# martinez.net
KiCad netlist of a schematic drawn in EAGLE
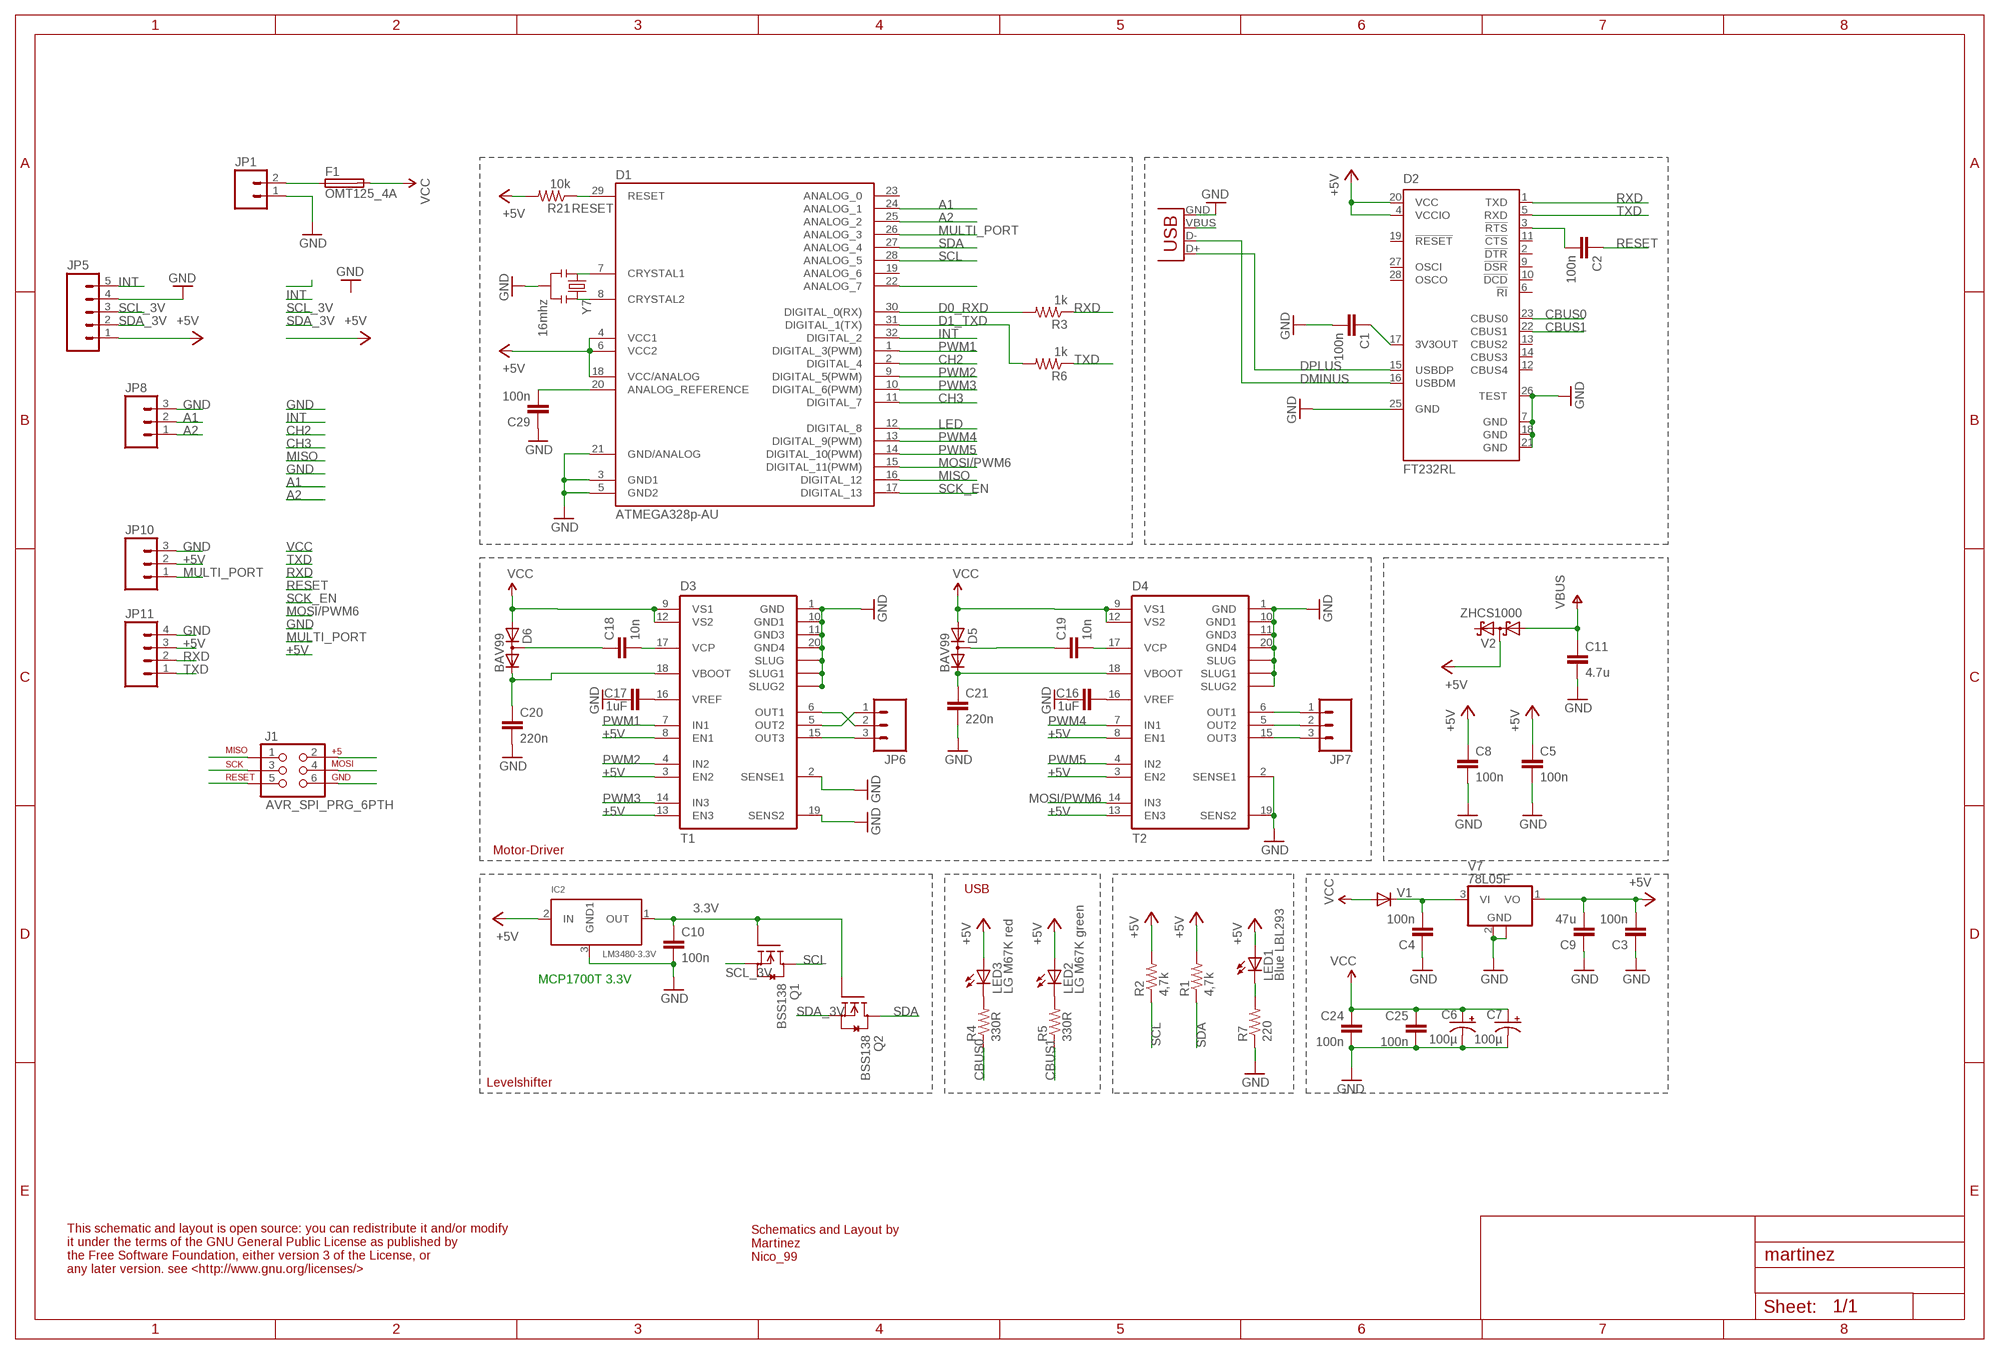
[diagram p0: schematic, sheet 1]

(export (version "E")
  (design (tool "Eeschema 10.0.6"))
  (components
    (comp (ref "C1")
      (value "100n")
      (footprint "eagle-import:0805")
      (libsource (lib "eagle-import") (part "CAP0805"))
    )
    (comp (ref "C2")
      (value "100n")
      (footprint "eagle-import:0805")
      (libsource (lib "eagle-import") (part "CAP0805"))
    )
    (comp (ref "C3")
      (value "100n")
      (footprint "eagle-import:0805")
      (libsource (lib "eagle-import") (part "CAP0805"))
    )
    (comp (ref "C4")
      (value "100n")
      (footprint "eagle-import:0805")
      (libsource (lib "eagle-import") (part "CAP0805"))
    )
    (comp (ref "C5")
      (value "100n")
      (footprint "eagle-import:0805")
      (libsource (lib "eagle-import") (part "CAP0805"))
    )
    (comp (ref "C6")
      (value "100µ")
      (footprint "eagle-import:PANASONIC_D")
      (libsource (lib "eagle-import") (part "CAP_POLD"))
    )
    (comp (ref "C7")
      (value "100µ")
      (footprint "eagle-import:PANASONIC_D")
      (libsource (lib "eagle-import") (part "CAP_POLD"))
    )
    (comp (ref "C8")
      (value "100n")
      (footprint "eagle-import:0805")
      (libsource (lib "eagle-import") (part "CAP0805"))
    )
    (comp (ref "C9")
      (value "47u")
      (footprint "eagle-import:C1210")
      (libsource (lib "eagle-import") (part "C-EUC1210"))
    )
    (comp (ref "C10")
      (value "100n")
      (footprint "eagle-import:0805")
      (libsource (lib "eagle-import") (part "CAP0805"))
    )
    (comp (ref "C11")
      (value "4.7u")
      (footprint "eagle-import:0805")
      (libsource (lib "eagle-import") (part "CAP0805"))
    )
    (comp (ref "C16")
      (value "1uF")
      (footprint "eagle-import:0805")
      (libsource (lib "eagle-import") (part "CAP0805"))
    )
    (comp (ref "C17")
      (value "1uF")
      (footprint "eagle-import:0805")
      (libsource (lib "eagle-import") (part "CAP0805"))
    )
    (comp (ref "C18")
      (value "10n")
      (footprint "eagle-import:0805")
      (libsource (lib "eagle-import") (part "CAP0805"))
    )
    (comp (ref "C19")
      (value "10n")
      (footprint "eagle-import:0805")
      (libsource (lib "eagle-import") (part "CAP0805"))
    )
    (comp (ref "C20")
      (value "220n")
      (footprint "eagle-import:0805")
      (libsource (lib "eagle-import") (part "CAP0805"))
    )
    (comp (ref "C21")
      (value "220n")
      (footprint "eagle-import:0805")
      (libsource (lib "eagle-import") (part "CAP0805"))
    )
    (comp (ref "C24")
      (value "100n")
      (footprint "eagle-import:0805")
      (libsource (lib "eagle-import") (part "CAP0805"))
    )
    (comp (ref "C25")
      (value "100n")
      (footprint "eagle-import:0805")
      (libsource (lib "eagle-import") (part "CAP0805"))
    )
    (comp (ref "C29")
      (value "100n")
      (footprint "eagle-import:0805")
      (libsource (lib "eagle-import") (part "CAP0805"))
    )
    (comp (ref "D1")
      (value "ATMEGA328p-AU")
      (footprint "eagle-import:TQFP32-08")
      (libsource (lib "eagle-import") (part "ATMEGA168-AU"))
    )
    (comp (ref "D2")
      (value "FT232RL")
      (footprint "eagle-import:SSOP28")
      (libsource (lib "eagle-import") (part "FT232RL"))
    )
    (comp (ref "D3")
      (value "T1")
      (footprint "eagle-import:SO20POWER2")
      (libsource (lib "eagle-import") (part "L6234"))
    )
    (comp (ref "D4")
      (value "T2")
      (footprint "eagle-import:SO20POWER2")
      (libsource (lib "eagle-import") (part "L6234"))
    )
    (comp (ref "D5")
      (value "BAV99")
      (footprint "eagle-import:SOT23")
      (libsource (lib "eagle-import") (part "BAV199"))
    )
    (comp (ref "D6")
      (value "BAV99")
      (footprint "eagle-import:SOT23")
      (libsource (lib "eagle-import") (part "BAV199"))
    )
    (comp (ref "F1")
      (value "OMT125_4A")
      (footprint "eagle-import:OMT125_11MM")
      (libsource (lib "eagle-import") (part "OMT125_11MM"))
    )
    (comp (ref "IC2")
      (value "LM3480-3.3V")
      (footprint "eagle-import:SOT23")
      (libsource (lib "eagle-import") (part "VREG_MULTI2"))
    )
    (comp (ref "J1")
      (value "AVR_SPI_PRG_6PTH")
      (footprint "eagle-import:2X3")
      (libsource (lib "eagle-import") (part "AVR_SPI_PRG_6PTH"))
    )
    (comp (ref "JP1")
      (value "M02PTH")
      (footprint "eagle-import:1X02")
      (libsource (lib "eagle-import") (part "M02PTH"))
    )
    (comp (ref "JP5")
      (value "M05PTH")
      (footprint "eagle-import:1X05")
      (libsource (lib "eagle-import") (part "M05PTH"))
    )
    (comp (ref "JP6")
      (value "M03PTH")
      (footprint "eagle-import:1X03")
      (libsource (lib "eagle-import") (part "M03PTH"))
    )
    (comp (ref "JP7")
      (value "M03PTH")
      (footprint "eagle-import:1X03")
      (libsource (lib "eagle-import") (part "M03PTH"))
    )
    (comp (ref "JP8")
      (value "M031X03_NO_SILK")
      (footprint "eagle-import:1X03_NO_SILK")
      (libsource (lib "eagle-import") (part "M031X03_NO_SILK"))
    )
    (comp (ref "JP10")
      (value "M031X03_NO_SILK")
      (footprint "eagle-import:1X03_NO_SILK")
      (libsource (lib "eagle-import") (part "M031X03_NO_SILK"))
    )
    (comp (ref "JP11")
      (value "M041X04_NO_SILK")
      (footprint "eagle-import:1X04_NO_SILK")
      (libsource (lib "eagle-import") (part "M041X04_NO_SILK"))
    )
    (comp (ref "LED1")
      (value "Blue LBL293")
      (footprint "eagle-import:CHIP-LED0603")
      (libsource (lib "eagle-import") (part "LEDCHIP-LED0603"))
    )
    (comp (ref "LED2")
      (value "LG M67K green")
      (footprint "eagle-import:CHIP-LED0805")
      (libsource (lib "eagle-import") (part "LEDCHIP-LED0805"))
    )
    (comp (ref "LED3")
      (value "LG M67K red")
      (footprint "eagle-import:CHIP-LED0805")
      (libsource (lib "eagle-import") (part "LEDCHIP-LED0805"))
    )
    (comp (ref "Q1")
      (value "BSS138")
      (footprint "eagle-import:SOT23")
      (libsource (lib "eagle-import") (part "BSS138"))
    )
    (comp (ref "Q2")
      (value "BSS138")
      (footprint "eagle-import:SOT23")
      (libsource (lib "eagle-import") (part "BSS138"))
    )
    (comp (ref "R1")
      (value "4,7k")
      (footprint "eagle-import:0805")
      (libsource (lib "eagle-import") (part "RESISTOR0805-RES"))
    )
    (comp (ref "R2")
      (value "4,7k")
      (footprint "eagle-import:0805")
      (libsource (lib "eagle-import") (part "RESISTOR0805-RES"))
    )
    (comp (ref "R3")
      (value "1k")
      (footprint "eagle-import:0805")
      (libsource (lib "eagle-import") (part "RESISTOR0805-RES"))
    )
    (comp (ref "R4")
      (value "330R")
      (footprint "eagle-import:0805")
      (libsource (lib "eagle-import") (part "RESISTOR0805-RES"))
    )
    (comp (ref "R5")
      (value "330R")
      (footprint "eagle-import:0805")
      (libsource (lib "eagle-import") (part "RESISTOR0805-RES"))
    )
    (comp (ref "R6")
      (value "1k")
      (footprint "eagle-import:0805")
      (libsource (lib "eagle-import") (part "RESISTOR0805-RES"))
    )
    (comp (ref "R7")
      (value "220")
      (footprint "eagle-import:0805")
      (libsource (lib "eagle-import") (part "RESISTOR0805-RES"))
    )
    (comp (ref "R21")
      (value "10k")
      (footprint "eagle-import:0805")
      (libsource (lib "eagle-import") (part "RESISTOR0805-RES"))
    )
    (comp (ref "V1")
      (value "DIODE-DO214AC")
      (footprint "eagle-import:DO214AC")
      (libsource (lib "eagle-import") (part "DIODE-DO214AC"))
    )
    (comp (ref "V2")
      (value "ZHCS1000")
      (footprint "eagle-import:SOT23")
      (libsource (lib "eagle-import") (part "BAS40-04"))
    )
    (comp (ref "V7")
      (value "78L05F")
      (footprint "eagle-import:SOT89")
      (libsource (lib "eagle-import") (part "78LF05"))
    )
    (comp (ref "X2")
      (value "USBOLD")
      (footprint "eagle-import:USB-MINIB-OLD")
      (libsource (lib "eagle-import") (part "USBOLD"))
    )
    (comp (ref "Y7")
      (value "16mhz")
      (footprint "eagle-import:RESONATOR-SMD")
      (libsource (lib "eagle-import") (part "RESONATORSMD"))
    )
  )
  (nets
    (net (code "1") (name "+5V") (class "Default")
      (node (ref "C3") (pin "2") (pinfunction "2_2") (pintype "passive"))
      (node (ref "C5") (pin "1") (pinfunction "1_1") (pintype "passive"))
      (node (ref "C8") (pin "1") (pinfunction "1_1") (pintype "passive"))
      (node (ref "C9") (pin "2") (pinfunction "2_2") (pintype "passive"))
      (node (ref "D1") (pin "18") (pinfunction "VCC/ANALOG_18") (pintype "passive"))
      (node (ref "D1") (pin "4") (pinfunction "VCC1_4") (pintype "power_in"))
      (node (ref "D1") (pin "6") (pinfunction "VCC2_6") (pintype "power_in"))
      (node (ref "D2") (pin "20") (pinfunction "VCC_20") (pintype "power_in"))
      (node (ref "D2") (pin "4") (pinfunction "VCCIO_4") (pintype "power_in"))
      (node (ref "D3") (pin "13") (pinfunction "EN3_13") (pintype "output"))
      (node (ref "D3") (pin "3") (pinfunction "EN2_3") (pintype "input"))
      (node (ref "D3") (pin "8") (pinfunction "EN1_8") (pintype "bidirectional"))
      (node (ref "D4") (pin "13") (pinfunction "EN3_13") (pintype "output"))
      (node (ref "D4") (pin "3") (pinfunction "EN2_3") (pintype "input"))
      (node (ref "D4") (pin "8") (pinfunction "EN1_8") (pintype "bidirectional"))
      (node (ref "IC2") (pin "2") (pinfunction "IN_2") (pintype "power_in"))
      (node (ref "J1") (pin "2") (pinfunction "2_2") (pintype "passive"))
      (node (ref "JP10") (pin "2") (pinfunction "2_2") (pintype "passive"))
      (node (ref "JP11") (pin "3") (pinfunction "3_3") (pintype "passive"))
      (node (ref "JP5") (pin "1") (pinfunction "1_1") (pintype "passive"))
      (node (ref "LED1") (pin "A") (pinfunction "A_A") (pintype "passive"))
      (node (ref "LED2") (pin "A") (pinfunction "A_A") (pintype "passive"))
      (node (ref "LED3") (pin "A") (pinfunction "A_A") (pintype "passive"))
      (node (ref "R1") (pin "2") (pinfunction "2_2") (pintype "passive"))
      (node (ref "R2") (pin "2") (pinfunction "2_2") (pintype "passive"))
      (node (ref "R21") (pin "2") (pinfunction "2_2") (pintype "passive"))
      (node (ref "V2") (pin "3") (pinfunction "C1A2_3") (pintype "passive"))
      (node (ref "V7") (pin "1") (pinfunction "VO_1") (pintype "passive"))
    )
    (net (code "2") (name "/3.3V") (class "Default")
      (node (ref "C10") (pin "1") (pinfunction "1_1") (pintype "passive"))
      (node (ref "IC2") (pin "1") (pinfunction "OUT_1") (pintype "power_in"))
      (node (ref "Q1") (pin "1") (pinfunction "G_1") (pintype "passive"))
      (node (ref "Q2") (pin "1") (pinfunction "G_1") (pintype "passive"))
    )
    (net (code "3") (name "/A1") (class "Default")
      (node (ref "D1") (pin "24") (pinfunction "ANALOG_1_24") (pintype "bidirectional"))
      (node (ref "JP8") (pin "2") (pinfunction "2_2") (pintype "passive"))
    )
    (net (code "4") (name "/A2") (class "Default")
      (node (ref "D1") (pin "25") (pinfunction "ANALOG_2_25") (pintype "bidirectional"))
      (node (ref "JP8") (pin "1") (pinfunction "1_1") (pintype "passive"))
    )
    (net (code "5") (name "/CBUS0") (class "Default")
      (node (ref "D2") (pin "23") (pinfunction "CBUS0_23") (pintype "bidirectional"))
      (node (ref "R4") (pin "1") (pinfunction "1_1") (pintype "passive"))
    )
    (net (code "6") (name "/CBUS1") (class "Default")
      (node (ref "D2") (pin "22") (pinfunction "CBUS1_22") (pintype "bidirectional"))
      (node (ref "R5") (pin "1") (pinfunction "1_1") (pintype "passive"))
    )
    (net (code "7") (name "/CH2") (class "Default")
      (node (ref "D1") (pin "2") (pinfunction "DIGITAL_4_2") (pintype "bidirectional"))
    )
    (net (code "8") (name "/CH3") (class "Default")
      (node (ref "D1") (pin "11") (pinfunction "DIGITAL_7_11") (pintype "bidirectional"))
    )
    (net (code "9") (name "/D0_RXD") (class "Default")
      (node (ref "D1") (pin "30") (pinfunction "DIGITAL_0(RX)_30") (pintype "bidirectional"))
      (node (ref "R3") (pin "2") (pinfunction "2_2") (pintype "passive"))
    )
    (net (code "10") (name "/D1_TXD") (class "Default")
      (node (ref "D1") (pin "31") (pinfunction "DIGITAL_1(TX)_31") (pintype "bidirectional"))
      (node (ref "R6") (pin "2") (pinfunction "2_2") (pintype "passive"))
    )
    (net (code "11") (name "/DMINUS") (class "Default")
      (node (ref "D2") (pin "16") (pinfunction "USBDM_16") (pintype "bidirectional"))
      (node (ref "X2") (pin "D-") (pinfunction "D-_D-") (pintype "bidirectional"))
    )
    (net (code "12") (name "/DPLUS") (class "Default")
      (node (ref "D2") (pin "15") (pinfunction "USBDP_15") (pintype "bidirectional"))
      (node (ref "X2") (pin "D+") (pinfunction "D+_D+") (pintype "bidirectional"))
    )
    (net (code "13") (name "/INT") (class "Default")
      (node (ref "D1") (pin "32") (pinfunction "DIGITAL_2_32") (pintype "bidirectional"))
      (node (ref "JP5") (pin "5") (pinfunction "5_5") (pintype "passive"))
    )
    (net (code "14") (name "/LED") (class "Default")
      (node (ref "D1") (pin "12") (pinfunction "DIGITAL_8_12") (pintype "bidirectional"))
    )
    (net (code "15") (name "/MISO") (class "Default")
      (node (ref "D1") (pin "16") (pinfunction "DIGITAL_12_16") (pintype "bidirectional"))
      (node (ref "J1") (pin "1") (pinfunction "1_1") (pintype "passive"))
    )
    (net (code "16") (name "/MOSI{slash}PWM6") (class "Default")
      (node (ref "D1") (pin "15") (pinfunction "DIGITAL_11(PWM)_15") (pintype "bidirectional"))
      (node (ref "D4") (pin "14") (pinfunction "IN3_14") (pintype "bidirectional"))
      (node (ref "J1") (pin "4") (pinfunction "4_4") (pintype "passive"))
    )
    (net (code "17") (name "/MULTI_PORT") (class "Default")
      (node (ref "D1") (pin "26") (pinfunction "ANALOG_3_26") (pintype "bidirectional"))
      (node (ref "JP10") (pin "1") (pinfunction "1_1") (pintype "passive"))
    )
    (net (code "18") (name "/PWM1") (class "Default")
      (node (ref "D1") (pin "1") (pinfunction "DIGITAL_3(PWM)_1") (pintype "bidirectional"))
      (node (ref "D3") (pin "7") (pinfunction "IN1_7") (pintype "input"))
    )
    (net (code "19") (name "/PWM2") (class "Default")
      (node (ref "D1") (pin "9") (pinfunction "DIGITAL_5(PWM)_9") (pintype "bidirectional"))
      (node (ref "D3") (pin "4") (pinfunction "IN2_4") (pintype "input"))
    )
    (net (code "20") (name "/PWM3") (class "Default")
      (node (ref "D1") (pin "10") (pinfunction "DIGITAL_6(PWM)_10") (pintype "bidirectional"))
      (node (ref "D3") (pin "14") (pinfunction "IN3_14") (pintype "bidirectional"))
    )
    (net (code "21") (name "/PWM4") (class "Default")
      (node (ref "D1") (pin "13") (pinfunction "DIGITAL_9(PWM)_13") (pintype "bidirectional"))
      (node (ref "D4") (pin "7") (pinfunction "IN1_7") (pintype "input"))
    )
    (net (code "22") (name "/PWM5") (class "Default")
      (node (ref "D1") (pin "14") (pinfunction "DIGITAL_10(PWM)_14") (pintype "bidirectional"))
      (node (ref "D4") (pin "4") (pinfunction "IN2_4") (pintype "input"))
    )
    (net (code "23") (name "/RESET") (class "Default")
      (node (ref "C2") (pin "1") (pinfunction "1_1") (pintype "passive"))
      (node (ref "D1") (pin "29") (pinfunction "RESET_29") (pintype "bidirectional"))
      (node (ref "J1") (pin "5") (pinfunction "5_5") (pintype "passive"))
      (node (ref "R21") (pin "1") (pinfunction "1_1") (pintype "passive"))
    )
    (net (code "24") (name "/RXD") (class "Default")
      (node (ref "D2") (pin "1") (pinfunction "TXD_1") (pintype "output"))
      (node (ref "JP11") (pin "2") (pinfunction "2_2") (pintype "passive"))
      (node (ref "R3") (pin "1") (pinfunction "1_1") (pintype "passive"))
    )
    (net (code "25") (name "/SCK_EN") (class "Default")
      (node (ref "D1") (pin "17") (pinfunction "DIGITAL_13_17") (pintype "bidirectional"))
      (node (ref "J1") (pin "3") (pinfunction "3_3") (pintype "passive"))
    )
    (net (code "26") (name "/SCL") (class "Default")
      (node (ref "D1") (pin "28") (pinfunction "ANALOG_5_28") (pintype "bidirectional"))
      (node (ref "Q1") (pin "3") (pinfunction "D_3") (pintype "passive"))
      (node (ref "R2") (pin "1") (pinfunction "1_1") (pintype "passive"))
    )
    (net (code "27") (name "/SCL_3V") (class "Default")
      (node (ref "JP5") (pin "3") (pinfunction "3_3") (pintype "passive"))
      (node (ref "Q1") (pin "2") (pinfunction "S_2") (pintype "passive"))
    )
    (net (code "28") (name "/SDA") (class "Default")
      (node (ref "D1") (pin "27") (pinfunction "ANALOG_4_27") (pintype "bidirectional"))
      (node (ref "Q2") (pin "3") (pinfunction "D_3") (pintype "passive"))
      (node (ref "R1") (pin "1") (pinfunction "1_1") (pintype "passive"))
    )
    (net (code "29") (name "/SDA_3V") (class "Default")
      (node (ref "JP5") (pin "2") (pinfunction "2_2") (pintype "passive"))
      (node (ref "Q2") (pin "2") (pinfunction "S_2") (pintype "passive"))
    )
    (net (code "30") (name "/TXD") (class "Default")
      (node (ref "D2") (pin "5") (pinfunction "RXD_5") (pintype "input"))
      (node (ref "JP11") (pin "1") (pinfunction "1_1") (pintype "passive"))
      (node (ref "R6") (pin "1") (pinfunction "1_1") (pintype "passive"))
    )
    (net (code "31") (name "GND") (class "Default")
      (node (ref "C1") (pin "2") (pinfunction "2_2") (pintype "passive"))
      (node (ref "C10") (pin "2") (pinfunction "2_2") (pintype "passive"))
      (node (ref "C11") (pin "2") (pinfunction "2_2") (pintype "passive"))
      (node (ref "C16") (pin "1") (pinfunction "1_1") (pintype "passive"))
      (node (ref "C17") (pin "1") (pinfunction "1_1") (pintype "passive"))
      (node (ref "C20") (pin "2") (pinfunction "2_2") (pintype "passive"))
      (node (ref "C21") (pin "2") (pinfunction "2_2") (pintype "passive"))
      (node (ref "C24") (pin "2") (pinfunction "2_2") (pintype "passive"))
      (node (ref "C25") (pin "2") (pinfunction "2_2") (pintype "passive"))
      (node (ref "C29") (pin "1") (pinfunction "1_1") (pintype "passive"))
      (node (ref "C3") (pin "1") (pinfunction "1_1") (pintype "passive"))
      (node (ref "C4") (pin "1") (pinfunction "1_1") (pintype "passive"))
      (node (ref "C5") (pin "2") (pinfunction "2_2") (pintype "passive"))
      (node (ref "C6") (pin "-") (pinfunction "-_-") (pintype "passive"))
      (node (ref "C7") (pin "-") (pinfunction "-_-") (pintype "passive"))
      (node (ref "C8") (pin "2") (pinfunction "2_2") (pintype "passive"))
      (node (ref "C9") (pin "1") (pinfunction "1_1") (pintype "passive"))
      (node (ref "D1") (pin "21") (pinfunction "GND/ANALOG_21") (pintype "power_in"))
      (node (ref "D1") (pin "3") (pinfunction "GND1_3") (pintype "power_in"))
      (node (ref "D1") (pin "5") (pinfunction "GND2_5") (pintype "power_in"))
      (node (ref "D2") (pin "18") (pinfunction "GND_18") (pintype "power_in"))
      (node (ref "D2") (pin "21") (pinfunction "GND_21") (pintype "power_in"))
      (node (ref "D2") (pin "25") (pinfunction "GND_25") (pintype "power_in"))
      (node (ref "D2") (pin "26") (pinfunction "TEST_26") (pintype "input"))
      (node (ref "D2") (pin "7") (pinfunction "GND_7") (pintype "power_in"))
      (node (ref "D3") (pin "1") (pinfunction "GND_1") (pintype "power_in"))
      (node (ref "D3") (pin "10") (pinfunction "GND1_10") (pintype "power_in"))
      (node (ref "D3") (pin "11") (pinfunction "GND3_11") (pintype "power_in"))
      (node (ref "D3") (pin "19") (pinfunction "SENS2_19") (pintype "power_in"))
      (node (ref "D3") (pin "2") (pinfunction "SENSE1_2") (pintype "output"))
      (node (ref "D3") (pin "20") (pinfunction "GND4_20") (pintype "power_in"))
      (node (ref "D3") (pin "SLUG") (pinfunction "SLUG1_SLUG") (pintype "power_in"))
      (node (ref "D3") (pin "SLUG1") (pinfunction "SLUG2_SLUG1") (pintype "power_in"))
      (node (ref "D3") (pin "SLUG2") (pinfunction "SLUG_SLUG2") (pintype "power_in"))
      (node (ref "D4") (pin "1") (pinfunction "GND_1") (pintype "power_in"))
      (node (ref "D4") (pin "10") (pinfunction "GND1_10") (pintype "power_in"))
      (node (ref "D4") (pin "11") (pinfunction "GND3_11") (pintype "power_in"))
      (node (ref "D4") (pin "19") (pinfunction "SENS2_19") (pintype "power_in"))
      (node (ref "D4") (pin "2") (pinfunction "SENSE1_2") (pintype "output"))
      (node (ref "D4") (pin "20") (pinfunction "GND4_20") (pintype "power_in"))
      (node (ref "D4") (pin "SLUG") (pinfunction "SLUG1_SLUG") (pintype "power_in"))
      (node (ref "D4") (pin "SLUG1") (pinfunction "SLUG2_SLUG1") (pintype "power_in"))
      (node (ref "D4") (pin "SLUG2") (pinfunction "SLUG_SLUG2") (pintype "power_in"))
      (node (ref "IC2") (pin "3") (pinfunction "GND1_3") (pintype "power_in"))
      (node (ref "J1") (pin "6") (pinfunction "6_6") (pintype "passive"))
      (node (ref "JP1") (pin "1") (pinfunction "1_1") (pintype "passive"))
      (node (ref "JP10") (pin "3") (pinfunction "3_3") (pintype "passive"))
      (node (ref "JP11") (pin "4") (pinfunction "4_4") (pintype "passive"))
      (node (ref "JP5") (pin "4") (pinfunction "4_4") (pintype "passive"))
      (node (ref "JP8") (pin "3") (pinfunction "3_3") (pintype "passive"))
      (node (ref "R7") (pin "1") (pinfunction "1_1") (pintype "passive"))
      (node (ref "V7") (pin "2") (pinfunction "GND_2") (pintype "passive"))
      (node (ref "V7") (pin "2@1") (pinfunction "GND_2@1") (pintype "passive"))
      (node (ref "X2") (pin "GND") (pinfunction "GND_GND") (pintype "bidirectional"))
      (node (ref "Y7") (pin "2") (pinfunction "2_2") (pintype "passive"))
    )
    (net (code "32") (name "Net-(D1-ANALOG_REFERENCE)") (class "Default")
      (node (ref "C29") (pin "2") (pinfunction "2_2") (pintype "passive"))
      (node (ref "D1") (pin "20") (pinfunction "ANALOG_REFERENCE_20") (pintype "passive"))
    )
    (net (code "33") (name "Net-(D1-CRYSTAL1)") (class "Default")
      (node (ref "D1") (pin "7") (pinfunction "CRYSTAL1_7") (pintype "bidirectional"))
      (node (ref "Y7") (pin "1") (pinfunction "1_1") (pintype "passive"))
    )
    (net (code "34") (name "Net-(D1-CRYSTAL2)") (class "Default")
      (node (ref "D1") (pin "8") (pinfunction "CRYSTAL2_8") (pintype "bidirectional"))
      (node (ref "Y7") (pin "3") (pinfunction "3_3") (pintype "passive"))
    )
    (net (code "35") (name "Net-(D2-3V3OUT)") (class "Default")
      (node (ref "C1") (pin "1") (pinfunction "1_1") (pintype "passive"))
      (node (ref "D2") (pin "17") (pinfunction "3V3OUT_17") (pintype "output"))
    )
    (net (code "36") (name "Net-(D2-~{RTS})") (class "Default")
      (node (ref "C2") (pin "2") (pinfunction "2_2") (pintype "passive"))
      (node (ref "D2") (pin "3") (pinfunction "~{RTS}_3") (pintype "output"))
    )
    (net (code "37") (name "Net-(D3-OUT1)") (class "Default")
      (node (ref "D3") (pin "6") (pinfunction "OUT1_6") (pintype "output"))
      (node (ref "JP6") (pin "2") (pinfunction "2_2") (pintype "passive"))
    )
    (net (code "38") (name "Net-(D3-OUT2)") (class "Default")
      (node (ref "D3") (pin "5") (pinfunction "OUT2_5") (pintype "output"))
      (node (ref "JP6") (pin "1") (pinfunction "1_1") (pintype "passive"))
    )
    (net (code "39") (name "Net-(D3-OUT3)") (class "Default")
      (node (ref "D3") (pin "15") (pinfunction "OUT3_15") (pintype "power_in"))
      (node (ref "JP6") (pin "3") (pinfunction "3_3") (pintype "passive"))
    )
    (net (code "40") (name "Net-(D3-VBOOT)") (class "Default")
      (node (ref "C20") (pin "1") (pinfunction "1_1") (pintype "passive"))
      (node (ref "D3") (pin "18") (pinfunction "VBOOT_18") (pintype "passive"))
      (node (ref "D6") (pin "2") (pinfunction "C_2") (pintype "passive"))
    )
    (net (code "41") (name "Net-(D3-VCP)") (class "Default")
      (node (ref "C18") (pin "2") (pinfunction "2_2") (pintype "passive"))
      (node (ref "D3") (pin "17") (pinfunction "VCP_17") (pintype "passive"))
    )
    (net (code "42") (name "Net-(D3-VREF)") (class "Default")
      (node (ref "C17") (pin "2") (pinfunction "2_2") (pintype "passive"))
      (node (ref "D3") (pin "16") (pinfunction "VREF_16") (pintype "input"))
    )
    (net (code "43") (name "Net-(D4-OUT1)") (class "Default")
      (node (ref "D4") (pin "6") (pinfunction "OUT1_6") (pintype "output"))
      (node (ref "JP7") (pin "1") (pinfunction "1_1") (pintype "passive"))
    )
    (net (code "44") (name "Net-(D4-OUT2)") (class "Default")
      (node (ref "D4") (pin "5") (pinfunction "OUT2_5") (pintype "output"))
      (node (ref "JP7") (pin "2") (pinfunction "2_2") (pintype "passive"))
    )
    (net (code "45") (name "Net-(D4-OUT3)") (class "Default")
      (node (ref "D4") (pin "15") (pinfunction "OUT3_15") (pintype "power_in"))
      (node (ref "JP7") (pin "3") (pinfunction "3_3") (pintype "passive"))
    )
    (net (code "46") (name "Net-(D4-VBOOT)") (class "Default")
      (node (ref "C21") (pin "1") (pinfunction "1_1") (pintype "passive"))
      (node (ref "D4") (pin "18") (pinfunction "VBOOT_18") (pintype "passive"))
      (node (ref "D5") (pin "2") (pinfunction "C_2") (pintype "passive"))
    )
    (net (code "47") (name "Net-(D4-VCP)") (class "Default")
      (node (ref "C19") (pin "2") (pinfunction "2_2") (pintype "passive"))
      (node (ref "D4") (pin "17") (pinfunction "VCP_17") (pintype "passive"))
    )
    (net (code "48") (name "Net-(D4-VREF)") (class "Default")
      (node (ref "C16") (pin "2") (pinfunction "2_2") (pintype "passive"))
      (node (ref "D4") (pin "16") (pinfunction "VREF_16") (pintype "input"))
    )
    (net (code "49") (name "Net-(D5-AC)") (class "Default")
      (node (ref "C19") (pin "1") (pinfunction "1_1") (pintype "passive"))
      (node (ref "D5") (pin "3") (pinfunction "AC_3") (pintype "passive"))
    )
    (net (code "50") (name "Net-(D6-AC)") (class "Default")
      (node (ref "C18") (pin "1") (pinfunction "1_1") (pintype "passive"))
      (node (ref "D6") (pin "3") (pinfunction "AC_3") (pintype "passive"))
    )
    (net (code "51") (name "Net-(F1-1)") (class "Default")
      (node (ref "F1") (pin "P$1") (pinfunction "1_P$1") (pintype "passive"))
      (node (ref "JP1") (pin "2") (pinfunction "2_2") (pintype "passive"))
    )
    (net (code "52") (name "Net-(LED1-PadC)") (class "Default")
      (node (ref "LED1") (pin "C") (pinfunction "C_C") (pintype "passive"))
      (node (ref "R7") (pin "2") (pinfunction "2_2") (pintype "passive"))
    )
    (net (code "53") (name "Net-(LED2-PadC)") (class "Default")
      (node (ref "LED2") (pin "C") (pinfunction "C_C") (pintype "passive"))
      (node (ref "R5") (pin "2") (pinfunction "2_2") (pintype "passive"))
    )
    (net (code "54") (name "Net-(LED3-PadC)") (class "Default")
      (node (ref "LED3") (pin "C") (pinfunction "C_C") (pintype "passive"))
      (node (ref "R4") (pin "2") (pinfunction "2_2") (pintype "passive"))
    )
    (net (code "55") (name "Net-(V7-VI)") (class "Default")
      (node (ref "C4") (pin "2") (pinfunction "2_2") (pintype "passive"))
      (node (ref "V1") (pin "C") (pinfunction "C_C") (pintype "passive"))
      (node (ref "V7") (pin "3") (pinfunction "VI_3") (pintype "input"))
    )
    (net (code "56") (name "VBUS") (class "Default")
      (node (ref "C11") (pin "1") (pinfunction "1_1") (pintype "passive"))
      (node (ref "V2") (pin "1") (pinfunction "A1_1") (pintype "passive"))
      (node (ref "X2") (pin "VBUS") (pinfunction "VBUS_VBUS") (pintype "bidirectional"))
    )
    (net (code "57") (name "VCC") (class "Default")
      (node (ref "C24") (pin "1") (pinfunction "1_1") (pintype "passive"))
      (node (ref "C25") (pin "1") (pinfunction "1_1") (pintype "passive"))
      (node (ref "C6") (pin "+") (pinfunction "+_+") (pintype "passive"))
      (node (ref "C7") (pin "+") (pinfunction "+_+") (pintype "passive"))
      (node (ref "D3") (pin "12") (pinfunction "VS2_12") (pintype "power_in"))
      (node (ref "D3") (pin "9") (pinfunction "VS1_9") (pintype "power_in"))
      (node (ref "D4") (pin "12") (pinfunction "VS2_12") (pintype "power_in"))
      (node (ref "D4") (pin "9") (pinfunction "VS1_9") (pintype "power_in"))
      (node (ref "D5") (pin "1") (pinfunction "A_1") (pintype "passive"))
      (node (ref "D6") (pin "1") (pinfunction "A_1") (pintype "passive"))
      (node (ref "F1") (pin "P$2") (pinfunction "2_P$2") (pintype "passive"))
      (node (ref "V1") (pin "A") (pinfunction "A_A") (pintype "passive"))
    )
    (net (code "58") (name "unconnected-(D1-ANALOG_0-Pad23)") (class "Default")
      (node (ref "D1") (pin "23") (pinfunction "ANALOG_0_23") (pintype "bidirectional"))
    )
    (net (code "59") (name "unconnected-(D1-ANALOG_6-Pad19)") (class "Default")
      (node (ref "D1") (pin "19") (pinfunction "ANALOG_6_19") (pintype "passive"))
    )
    (net (code "60") (name "unconnected-(D1-ANALOG_7-Pad22)") (class "Default")
      (node (ref "D1") (pin "22") (pinfunction "ANALOG_7_22") (pintype "passive"))
    )
    (net (code "61") (name "unconnected-(D2-CBUS2-Pad13)") (class "Default")
      (node (ref "D2") (pin "13") (pinfunction "CBUS2_13") (pintype "bidirectional"))
    )
    (net (code "62") (name "unconnected-(D2-CBUS3-Pad14)") (class "Default")
      (node (ref "D2") (pin "14") (pinfunction "CBUS3_14") (pintype "bidirectional"))
    )
    (net (code "63") (name "unconnected-(D2-CBUS4-Pad12)") (class "Default")
      (node (ref "D2") (pin "12") (pinfunction "CBUS4_12") (pintype "bidirectional"))
    )
    (net (code "64") (name "unconnected-(D2-OSCI-Pad27)") (class "Default")
      (node (ref "D2") (pin "27") (pinfunction "OSCI_27") (pintype "input"))
    )
    (net (code "65") (name "unconnected-(D2-OSCO-Pad28)") (class "Default")
      (node (ref "D2") (pin "28") (pinfunction "OSCO_28") (pintype "output"))
    )
    (net (code "66") (name "unconnected-(D2-~{CTS}-Pad11)") (class "Default")
      (node (ref "D2") (pin "11") (pinfunction "~{CTS}_11") (pintype "input"))
    )
    (net (code "67") (name "unconnected-(D2-~{DCD}-Pad10)") (class "Default")
      (node (ref "D2") (pin "10") (pinfunction "~{DCD}_10") (pintype "input"))
    )
    (net (code "68") (name "unconnected-(D2-~{DSR}-Pad9)") (class "Default")
      (node (ref "D2") (pin "9") (pinfunction "~{DSR}_9") (pintype "input"))
    )
    (net (code "69") (name "unconnected-(D2-~{DTR}-Pad2)") (class "Default")
      (node (ref "D2") (pin "2") (pinfunction "~{DTR}_2") (pintype "output"))
    )
    (net (code "70") (name "unconnected-(D2-~{RESET}-Pad19)") (class "Default")
      (node (ref "D2") (pin "19") (pinfunction "~{RESET}_19") (pintype "input"))
    )
    (net (code "71") (name "unconnected-(D2-~{RI}-Pad6)") (class "Default")
      (node (ref "D2") (pin "6") (pinfunction "~{RI}_6") (pintype "input"))
    )
    (net (code "72") (name "unconnected-(V2-C2-Pad2)") (class "Default")
      (node (ref "V2") (pin "2") (pinfunction "C2_2") (pintype "passive"))
    )
  )
)
